# Snow_Melt_Map_2.net
KiCad netlist of a schematic drawn in EAGLE
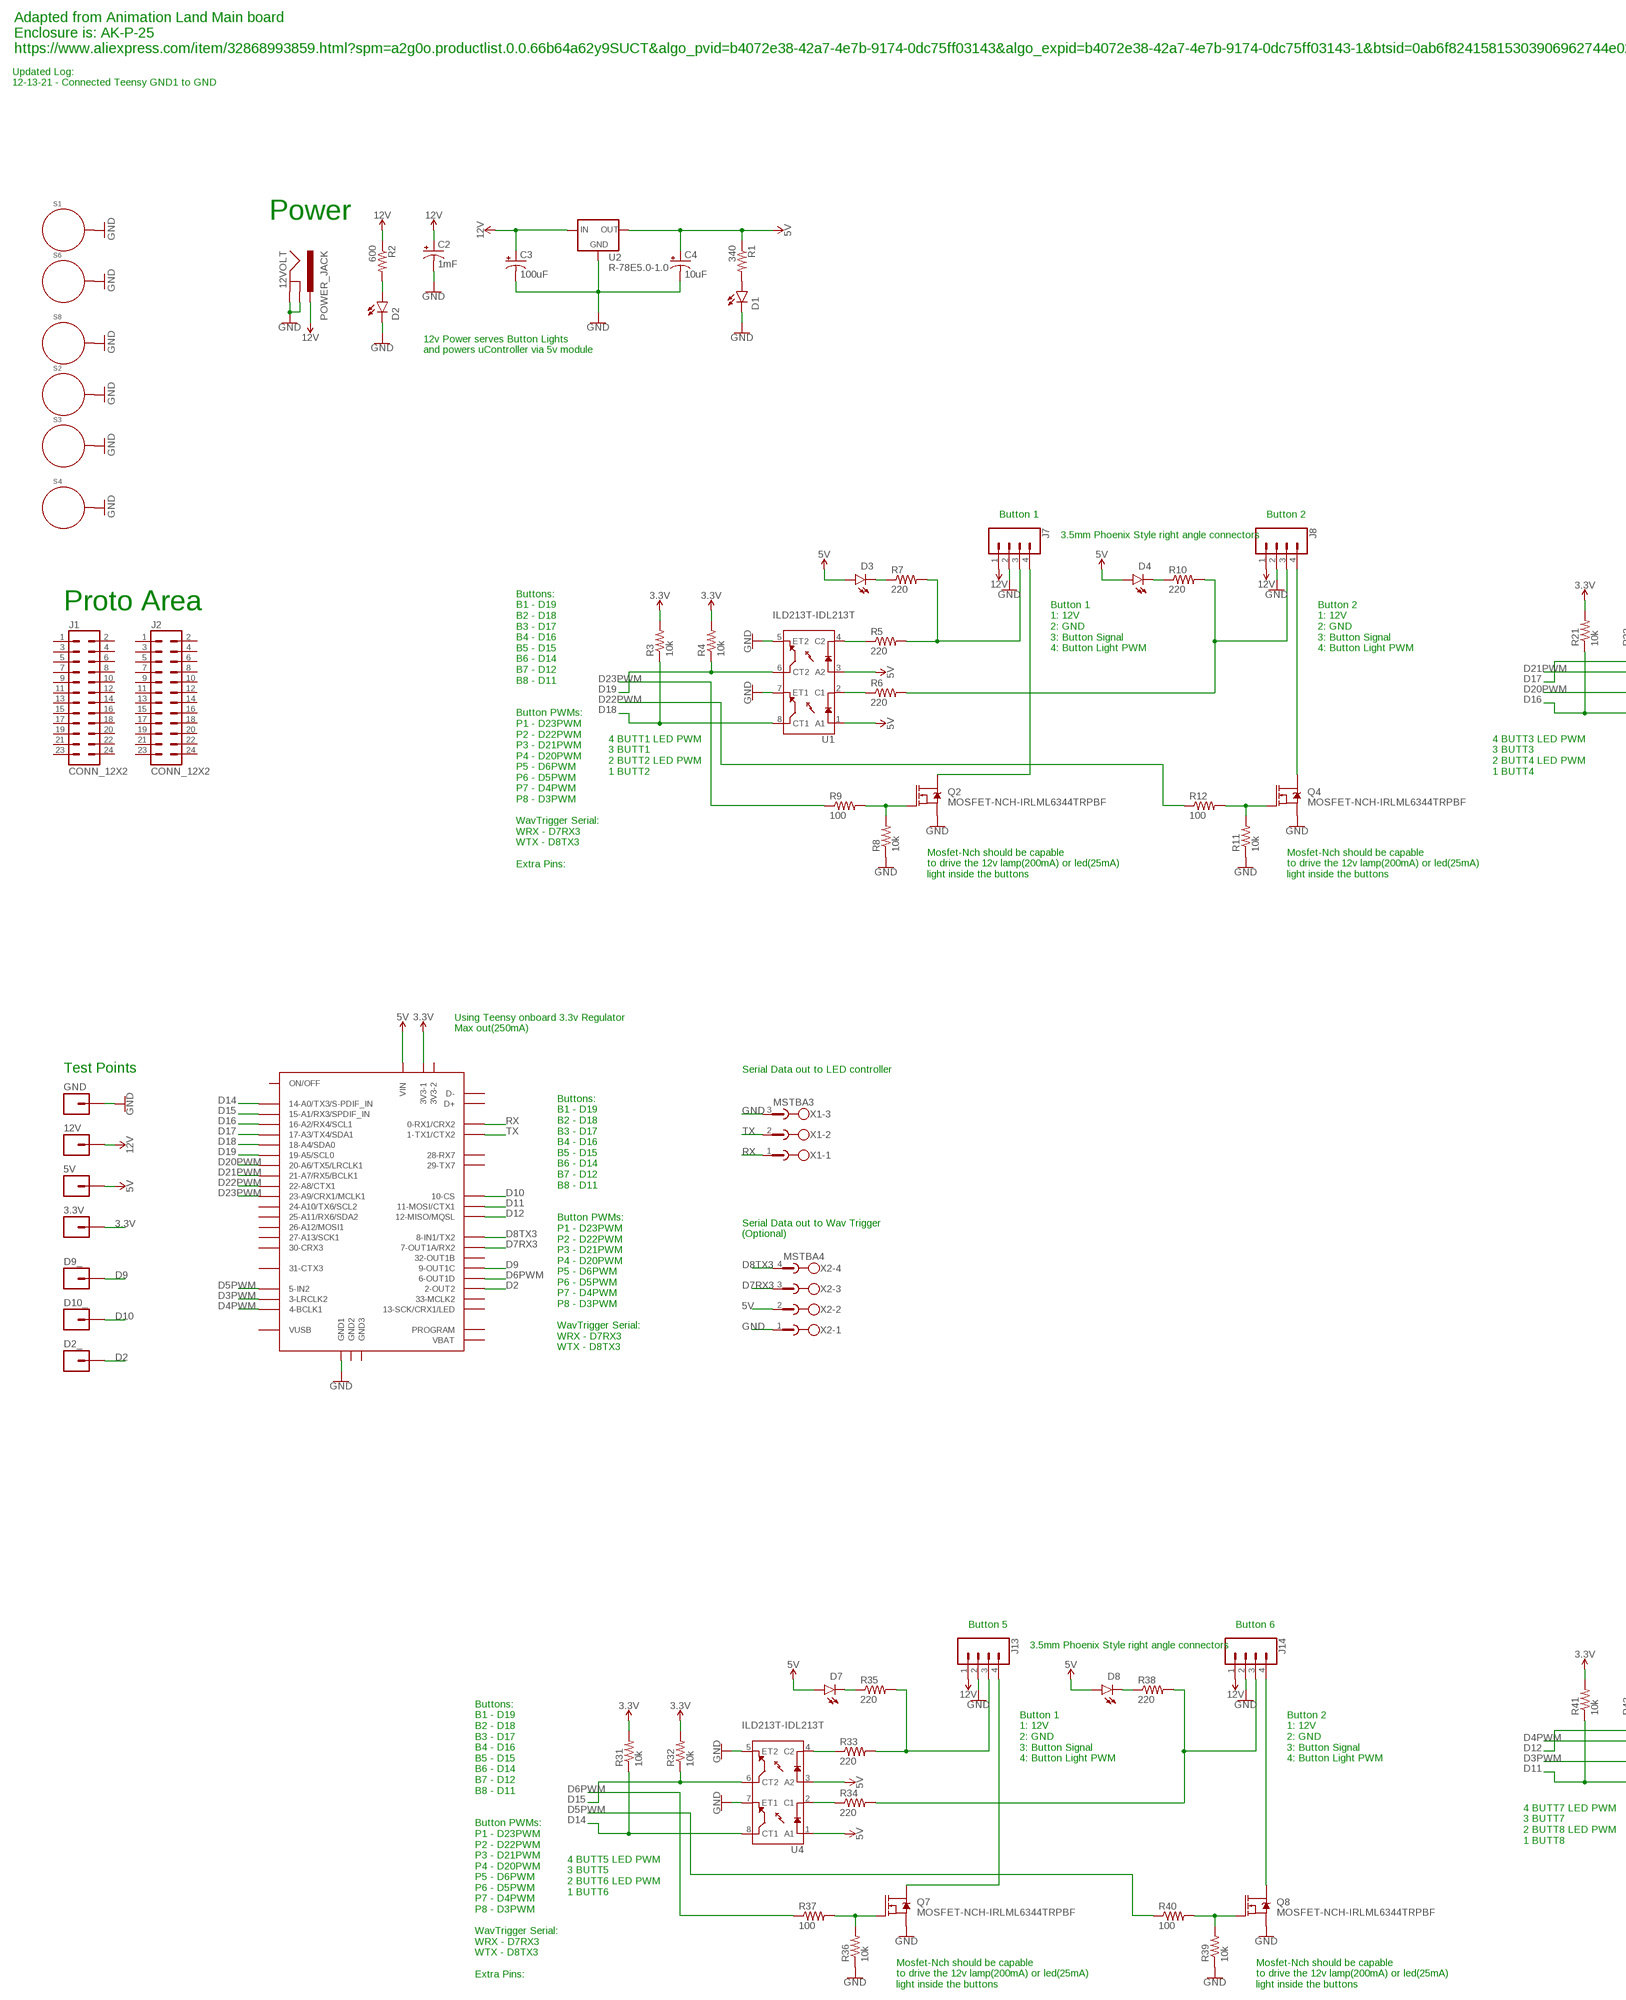
[diagram p0: schematic, sheet 1, part 1 of 2]
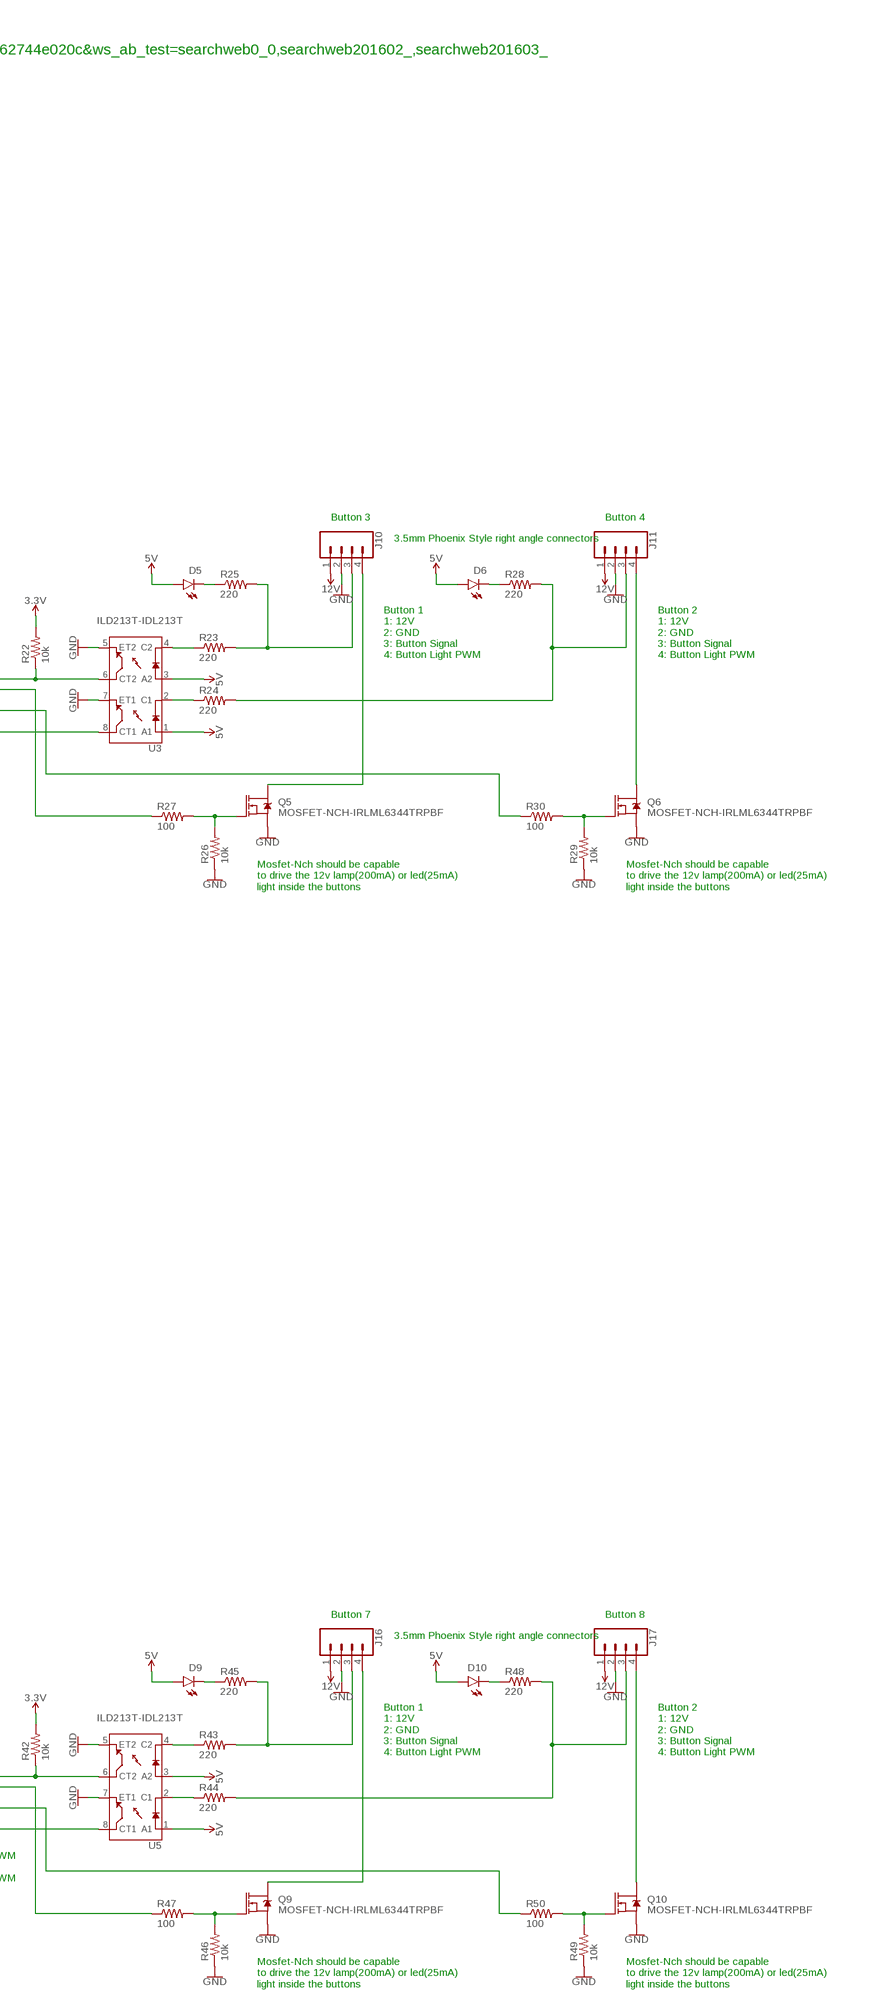
[diagram p1: schematic, sheet 1, part 2 of 2]

(export (version "E")
  (design (tool "Eeschema 10.0.6"))
  (components
    (comp (ref "3.3V")
      (value "M01PTH")
      (footprint "eagle-import:1X01")
      (libsource (lib "eagle-import") (part "M01PTH"))
    )
    (comp (ref "5V")
      (value "M01PTH")
      (footprint "eagle-import:1X01")
      (libsource (lib "eagle-import") (part "M01PTH"))
    )
    (comp (ref "12V")
      (value "M01PTH")
      (footprint "eagle-import:1X01")
      (libsource (lib "eagle-import") (part "M01PTH"))
    )
    (comp (ref "12VOLT")
      (value "POWER_JACK")
      (footprint "eagle-import:POWER_JACK_PTH")
      (libsource (lib "eagle-import") (part "POWER_JACK"))
    )
    (comp (ref "C2")
      (value "1mF")
      (footprint "eagle-import:CPOL-RADIAL-5MM-10MM")
      (libsource (lib "eagle-import") (part "1000UF-RADIAL-5MM-25V-20%"))
    )
    (comp (ref "C3")
      (value "100uF")
      (footprint "eagle-import:CPOL-RADIAL-2.5MM-6.5MM")
      (libsource (lib "eagle-import") (part "100UF-POLAR-RADIAL-2.5MM-25V-20%"))
    )
    (comp (ref "C4")
      (value "10uF")
      (footprint "eagle-import:CPOL-RADIAL-2.5MM-5MM-KIT")
      (libsource (lib "eagle-import") (part "10UF-POLAR-RADIAL-2.5MM-KIT-25V-20%"))
    )
    (comp (ref "D1")
      (value "RED")
      (footprint "eagle-import:LED-1206")
      (libsource (lib "eagle-import") (part "LED-RED1206"))
    )
    (comp (ref "D2")
      (value "RED")
      (footprint "eagle-import:LED-1206")
      (libsource (lib "eagle-import") (part "LED-RED1206"))
    )
    (comp (ref "D2_")
      (value "M01PTH")
      (footprint "eagle-import:1X01")
      (libsource (lib "eagle-import") (part "M01PTH"))
    )
    (comp (ref "D3")
      (value "RED")
      (footprint "eagle-import:LED-1206")
      (libsource (lib "eagle-import") (part "LED-RED1206"))
    )
    (comp (ref "D4")
      (value "RED")
      (footprint "eagle-import:LED-1206")
      (libsource (lib "eagle-import") (part "LED-RED1206"))
    )
    (comp (ref "D5")
      (value "RED")
      (footprint "eagle-import:LED-1206")
      (libsource (lib "eagle-import") (part "LED-RED1206"))
    )
    (comp (ref "D6")
      (value "RED")
      (footprint "eagle-import:LED-1206")
      (libsource (lib "eagle-import") (part "LED-RED1206"))
    )
    (comp (ref "D7")
      (value "RED")
      (footprint "eagle-import:LED-1206")
      (libsource (lib "eagle-import") (part "LED-RED1206"))
    )
    (comp (ref "D8")
      (value "RED")
      (footprint "eagle-import:LED-1206")
      (libsource (lib "eagle-import") (part "LED-RED1206"))
    )
    (comp (ref "D9")
      (value "RED")
      (footprint "eagle-import:LED-1206")
      (libsource (lib "eagle-import") (part "LED-RED1206"))
    )
    (comp (ref "D9_")
      (value "M01PTH")
      (footprint "eagle-import:1X01")
      (libsource (lib "eagle-import") (part "M01PTH"))
    )
    (comp (ref "D10")
      (value "RED")
      (footprint "eagle-import:LED-1206")
      (libsource (lib "eagle-import") (part "LED-RED1206"))
    )
    (comp (ref "D10_")
      (value "M01PTH")
      (footprint "eagle-import:1X01")
      (libsource (lib "eagle-import") (part "M01PTH"))
    )
    (comp (ref "GND")
      (value "M01PTH")
      (footprint "eagle-import:1X01")
      (libsource (lib "eagle-import") (part "M01PTH"))
    )
    (comp (ref "J1")
      (value "CONN_12X2")
      (footprint "eagle-import:2X12")
      (libsource (lib "eagle-import") (part "CONN_12X2"))
    )
    (comp (ref "J2")
      (value "CONN_12X2")
      (footprint "eagle-import:2X12")
      (libsource (lib "eagle-import") (part "CONN_12X2"))
    )
    (comp (ref "J7")
      (value "CONN_043.5MM_RA")
      (footprint "eagle-import:1X04_3.5MM_RA")
      (libsource (lib "eagle-import") (part "CONN_043.5MM_RA"))
    )
    (comp (ref "J8")
      (value "CONN_043.5MM_RA")
      (footprint "eagle-import:1X04_3.5MM_RA")
      (libsource (lib "eagle-import") (part "CONN_043.5MM_RA"))
    )
    (comp (ref "J10")
      (value "CONN_043.5MM_RA")
      (footprint "eagle-import:1X04_3.5MM_RA")
      (libsource (lib "eagle-import") (part "CONN_043.5MM_RA"))
    )
    (comp (ref "J11")
      (value "CONN_043.5MM_RA")
      (footprint "eagle-import:1X04_3.5MM_RA")
      (libsource (lib "eagle-import") (part "CONN_043.5MM_RA"))
    )
    (comp (ref "J13")
      (value "CONN_043.5MM_RA")
      (footprint "eagle-import:1X04_3.5MM_RA")
      (libsource (lib "eagle-import") (part "CONN_043.5MM_RA"))
    )
    (comp (ref "J14")
      (value "CONN_043.5MM_RA")
      (footprint "eagle-import:1X04_3.5MM_RA")
      (libsource (lib "eagle-import") (part "CONN_043.5MM_RA"))
    )
    (comp (ref "J16")
      (value "CONN_043.5MM_RA")
      (footprint "eagle-import:1X04_3.5MM_RA")
      (libsource (lib "eagle-import") (part "CONN_043.5MM_RA"))
    )
    (comp (ref "J17")
      (value "CONN_043.5MM_RA")
      (footprint "eagle-import:1X04_3.5MM_RA")
      (libsource (lib "eagle-import") (part "CONN_043.5MM_RA"))
    )
    (comp (ref "Q2")
      (value "MOSFET-NCH-IRLML6344TRPBF")
      (footprint "eagle-import:SOT23-3")
      (libsource (lib "eagle-import") (part "MOSFET-NCH-IRLML6344TRPBF"))
    )
    (comp (ref "Q4")
      (value "MOSFET-NCH-IRLML6344TRPBF")
      (footprint "eagle-import:SOT23-3")
      (libsource (lib "eagle-import") (part "MOSFET-NCH-IRLML6344TRPBF"))
    )
    (comp (ref "Q5")
      (value "MOSFET-NCH-IRLML6344TRPBF")
      (footprint "eagle-import:SOT23-3")
      (libsource (lib "eagle-import") (part "MOSFET-NCH-IRLML6344TRPBF"))
    )
    (comp (ref "Q6")
      (value "MOSFET-NCH-IRLML6344TRPBF")
      (footprint "eagle-import:SOT23-3")
      (libsource (lib "eagle-import") (part "MOSFET-NCH-IRLML6344TRPBF"))
    )
    (comp (ref "Q7")
      (value "MOSFET-NCH-IRLML6344TRPBF")
      (footprint "eagle-import:SOT23-3")
      (libsource (lib "eagle-import") (part "MOSFET-NCH-IRLML6344TRPBF"))
    )
    (comp (ref "Q8")
      (value "MOSFET-NCH-IRLML6344TRPBF")
      (footprint "eagle-import:SOT23-3")
      (libsource (lib "eagle-import") (part "MOSFET-NCH-IRLML6344TRPBF"))
    )
    (comp (ref "Q9")
      (value "MOSFET-NCH-IRLML6344TRPBF")
      (footprint "eagle-import:SOT23-3")
      (libsource (lib "eagle-import") (part "MOSFET-NCH-IRLML6344TRPBF"))
    )
    (comp (ref "Q10")
      (value "MOSFET-NCH-IRLML6344TRPBF")
      (footprint "eagle-import:SOT23-3")
      (libsource (lib "eagle-import") (part "MOSFET-NCH-IRLML6344TRPBF"))
    )
    (comp (ref "R1")
      (value "340")
      (footprint "eagle-import:R0805")
      (libsource (lib "eagle-import") (part "R-US_R0805"))
    )
    (comp (ref "R2")
      (value "600")
      (footprint "eagle-import:R0805")
      (libsource (lib "eagle-import") (part "R-US_R0805"))
    )
    (comp (ref "R3")
      (value "10k")
      (footprint "eagle-import:R0805")
      (libsource (lib "eagle-import") (part "R-US_R0805"))
    )
    (comp (ref "R4")
      (value "10k")
      (footprint "eagle-import:R0805")
      (libsource (lib "eagle-import") (part "R-US_R0805"))
    )
    (comp (ref "R5")
      (value "220")
      (footprint "eagle-import:R0805")
      (libsource (lib "eagle-import") (part "R-US_R0805"))
    )
    (comp (ref "R6")
      (value "220")
      (footprint "eagle-import:R0805")
      (libsource (lib "eagle-import") (part "R-US_R0805"))
    )
    (comp (ref "R7")
      (value "220")
      (footprint "eagle-import:R0805")
      (libsource (lib "eagle-import") (part "R-US_R0805"))
    )
    (comp (ref "R8")
      (value "10k")
      (footprint "eagle-import:R0805")
      (libsource (lib "eagle-import") (part "R-US_R0805"))
    )
    (comp (ref "R9")
      (value "100")
      (footprint "eagle-import:R0805")
      (libsource (lib "eagle-import") (part "R-US_R0805"))
    )
    (comp (ref "R10")
      (value "220")
      (footprint "eagle-import:R0805")
      (libsource (lib "eagle-import") (part "R-US_R0805"))
    )
    (comp (ref "R11")
      (value "10k")
      (footprint "eagle-import:R0805")
      (libsource (lib "eagle-import") (part "R-US_R0805"))
    )
    (comp (ref "R12")
      (value "100")
      (footprint "eagle-import:R0805")
      (libsource (lib "eagle-import") (part "R-US_R0805"))
    )
    (comp (ref "R21")
      (value "10k")
      (footprint "eagle-import:R0805")
      (libsource (lib "eagle-import") (part "R-US_R0805"))
    )
    (comp (ref "R22")
      (value "10k")
      (footprint "eagle-import:R0805")
      (libsource (lib "eagle-import") (part "R-US_R0805"))
    )
    (comp (ref "R23")
      (value "220")
      (footprint "eagle-import:R0805")
      (libsource (lib "eagle-import") (part "R-US_R0805"))
    )
    (comp (ref "R24")
      (value "220")
      (footprint "eagle-import:R0805")
      (libsource (lib "eagle-import") (part "R-US_R0805"))
    )
    (comp (ref "R25")
      (value "220")
      (footprint "eagle-import:R0805")
      (libsource (lib "eagle-import") (part "R-US_R0805"))
    )
    (comp (ref "R26")
      (value "10k")
      (footprint "eagle-import:R0805")
      (libsource (lib "eagle-import") (part "R-US_R0805"))
    )
    (comp (ref "R27")
      (value "100")
      (footprint "eagle-import:R0805")
      (libsource (lib "eagle-import") (part "R-US_R0805"))
    )
    (comp (ref "R28")
      (value "220")
      (footprint "eagle-import:R0805")
      (libsource (lib "eagle-import") (part "R-US_R0805"))
    )
    (comp (ref "R29")
      (value "10k")
      (footprint "eagle-import:R0805")
      (libsource (lib "eagle-import") (part "R-US_R0805"))
    )
    (comp (ref "R30")
      (value "100")
      (footprint "eagle-import:R0805")
      (libsource (lib "eagle-import") (part "R-US_R0805"))
    )
    (comp (ref "R31")
      (value "10k")
      (footprint "eagle-import:R0805")
      (libsource (lib "eagle-import") (part "R-US_R0805"))
    )
    (comp (ref "R32")
      (value "10k")
      (footprint "eagle-import:R0805")
      (libsource (lib "eagle-import") (part "R-US_R0805"))
    )
    (comp (ref "R33")
      (value "220")
      (footprint "eagle-import:R0805")
      (libsource (lib "eagle-import") (part "R-US_R0805"))
    )
    (comp (ref "R34")
      (value "220")
      (footprint "eagle-import:R0805")
      (libsource (lib "eagle-import") (part "R-US_R0805"))
    )
    (comp (ref "R35")
      (value "220")
      (footprint "eagle-import:R0805")
      (libsource (lib "eagle-import") (part "R-US_R0805"))
    )
    (comp (ref "R36")
      (value "10k")
      (footprint "eagle-import:R0805")
      (libsource (lib "eagle-import") (part "R-US_R0805"))
    )
    (comp (ref "R37")
      (value "100")
      (footprint "eagle-import:R0805")
      (libsource (lib "eagle-import") (part "R-US_R0805"))
    )
    (comp (ref "R38")
      (value "220")
      (footprint "eagle-import:R0805")
      (libsource (lib "eagle-import") (part "R-US_R0805"))
    )
    (comp (ref "R39")
      (value "10k")
      (footprint "eagle-import:R0805")
      (libsource (lib "eagle-import") (part "R-US_R0805"))
    )
    (comp (ref "R40")
      (value "100")
      (footprint "eagle-import:R0805")
      (libsource (lib "eagle-import") (part "R-US_R0805"))
    )
    (comp (ref "R41")
      (value "10k")
      (footprint "eagle-import:R0805")
      (libsource (lib "eagle-import") (part "R-US_R0805"))
    )
    (comp (ref "R42")
      (value "10k")
      (footprint "eagle-import:R0805")
      (libsource (lib "eagle-import") (part "R-US_R0805"))
    )
    (comp (ref "R43")
      (value "220")
      (footprint "eagle-import:R0805")
      (libsource (lib "eagle-import") (part "R-US_R0805"))
    )
    (comp (ref "R44")
      (value "220")
      (footprint "eagle-import:R0805")
      (libsource (lib "eagle-import") (part "R-US_R0805"))
    )
    (comp (ref "R45")
      (value "220")
      (footprint "eagle-import:R0805")
      (libsource (lib "eagle-import") (part "R-US_R0805"))
    )
    (comp (ref "R46")
      (value "10k")
      (footprint "eagle-import:R0805")
      (libsource (lib "eagle-import") (part "R-US_R0805"))
    )
    (comp (ref "R47")
      (value "100")
      (footprint "eagle-import:R0805")
      (libsource (lib "eagle-import") (part "R-US_R0805"))
    )
    (comp (ref "R48")
      (value "220")
      (footprint "eagle-import:R0805")
      (libsource (lib "eagle-import") (part "R-US_R0805"))
    )
    (comp (ref "R49")
      (value "10k")
      (footprint "eagle-import:R0805")
      (libsource (lib "eagle-import") (part "R-US_R0805"))
    )
    (comp (ref "R50")
      (value "100")
      (footprint "eagle-import:R0805")
      (libsource (lib "eagle-import") (part "R-US_R0805"))
    )
    (comp (ref "S1")
      (value "STANDOFF_ELECTRICAL5-32")
      (footprint "eagle-import:STANDOFF_ELECTRICAL_5_32")
      (libsource (lib "eagle-import") (part "STANDOFF_ELECTRICAL5-32"))
    )
    (comp (ref "S2")
      (value "STANDOFF_ELECTRICAL5-32")
      (footprint "eagle-import:STANDOFF_ELECTRICAL_5_32")
      (libsource (lib "eagle-import") (part "STANDOFF_ELECTRICAL5-32"))
    )
    (comp (ref "S3")
      (value "STANDOFF_ELECTRICAL5-32")
      (footprint "eagle-import:STANDOFF_ELECTRICAL_5_32")
      (libsource (lib "eagle-import") (part "STANDOFF_ELECTRICAL5-32"))
    )
    (comp (ref "S4")
      (value "STANDOFF_ELECTRICAL5-32")
      (footprint "eagle-import:STANDOFF_ELECTRICAL_5_32")
      (libsource (lib "eagle-import") (part "STANDOFF_ELECTRICAL5-32"))
    )
    (comp (ref "S6")
      (value "STANDOFF_ELECTRICAL5-32")
      (footprint "eagle-import:STANDOFF_ELECTRICAL_5_32")
      (libsource (lib "eagle-import") (part "STANDOFF_ELECTRICAL5-32"))
    )
    (comp (ref "S8")
      (value "STANDOFF_ELECTRICAL5-32")
      (footprint "eagle-import:STANDOFF_ELECTRICAL_5_32")
      (libsource (lib "eagle-import") (part "STANDOFF_ELECTRICAL5-32"))
    )
    (comp (ref "U$1")
      (value "TEENSY40")
      (footprint "eagle-import:TEENSY40")
      (libsource (lib "eagle-import") (part "TEENSY40"))
    )
    (comp (ref "U1")
      (value "ILD213T-IDL213T")
      (footprint "eagle-import:SO08")
      (libsource (lib "eagle-import") (part "ILD213T-IDL213T"))
    )
    (comp (ref "U2")
      (value "R-78E5.0-1.0")
      (footprint "eagle-import:DC-DC_CONVERTER_78XX")
      (libsource (lib "eagle-import") (part "R-78E5.0-1.0"))
    )
    (comp (ref "U3")
      (value "ILD213T-IDL213T")
      (footprint "eagle-import:SO08")
      (libsource (lib "eagle-import") (part "ILD213T-IDL213T"))
    )
    (comp (ref "U4")
      (value "ILD213T-IDL213T")
      (footprint "eagle-import:SO08")
      (libsource (lib "eagle-import") (part "ILD213T-IDL213T"))
    )
    (comp (ref "U5")
      (value "ILD213T-IDL213T")
      (footprint "eagle-import:SO08")
      (libsource (lib "eagle-import") (part "ILD213T-IDL213T"))
    )
    (comp (ref "X1")
      (value "MSTBA3")
      (footprint "eagle-import:MSTBA3")
      (fields (field (name "MF") "FARNELL") (field (name "MPN") "1757255"))
      (libsource (lib "eagle-import") (part "MSTBA3"))
    )
    (comp (ref "X2")
      (value "MSTBA4")
      (footprint "eagle-import:MSTBA4")
      (fields (field (name "MF") "FARNELL") (field (name "MPN") "1757268"))
      (libsource (lib "eagle-import") (part "MSTBA4"))
    )
  )
  (nets
    (net (code "1") (name "/D2") (class "Default")
      (node (ref "D2_") (pin "1") (pinfunction "1_1") (pintype "passive"))
      (node (ref "U$1") (pin "2-OUT2") (pinfunction "2-OUT2_2-OUT2") (pintype "bidirectional"))
    )
    (net (code "2") (name "/D3PWM") (class "Default")
      (node (ref "R50") (pin "1") (pinfunction "1_1") (pintype "passive"))
      (node (ref "U$1") (pin "3-LRCLK2") (pinfunction "3-LRCLK2_3-LRCLK2") (pintype "bidirectional"))
    )
    (net (code "3") (name "/D4PWM") (class "Default")
      (node (ref "R47") (pin "1") (pinfunction "1_1") (pintype "passive"))
      (node (ref "U$1") (pin "4-BCLK2") (pinfunction "4-BCLK1_4-BCLK2") (pintype "bidirectional"))
    )
    (net (code "4") (name "/D5PWM") (class "Default")
      (node (ref "R40") (pin "1") (pinfunction "1_1") (pintype "passive"))
      (node (ref "U$1") (pin "5-IN2") (pinfunction "5-IN2_5-IN2") (pintype "bidirectional"))
    )
    (net (code "5") (name "/D6PWM") (class "Default")
      (node (ref "R37") (pin "1") (pinfunction "1_1") (pintype "passive"))
      (node (ref "U$1") (pin "6-OUT1D") (pinfunction "6-OUT1D_6-OUT1D") (pintype "bidirectional"))
    )
    (net (code "6") (name "/D7RX3") (class "Default")
      (node (ref "U$1") (pin "7-RX2/OUT1A") (pinfunction "7-OUT1A/RX2_7-RX2/OUT1A") (pintype "bidirectional"))
      (node (ref "X2") (pin "3") (pinfunction "1_3") (pintype "passive"))
    )
    (net (code "7") (name "/D8TX3") (class "Default")
      (node (ref "U$1") (pin "8-TX2/IN1") (pinfunction "8-IN1/TX2_8-TX2/IN1") (pintype "bidirectional"))
      (node (ref "X2") (pin "4") (pinfunction "1_4") (pintype "passive"))
    )
    (net (code "8") (name "/D9") (class "Default")
      (node (ref "D9_") (pin "1") (pinfunction "1_1") (pintype "passive"))
      (node (ref "U$1") (pin "9-OUT1C") (pinfunction "9-OUT1C_9-OUT1C") (pintype "bidirectional"))
    )
    (net (code "9") (name "/D10") (class "Default")
      (node (ref "D10_") (pin "1") (pinfunction "1_1") (pintype "passive"))
      (node (ref "U$1") (pin "10-CS/MQSR") (pinfunction "10-CS_10-CS/MQSR") (pintype "bidirectional"))
    )
    (net (code "10") (name "/D11") (class "Default")
      (node (ref "R41") (pin "1") (pinfunction "1_1") (pintype "passive"))
      (node (ref "U$1") (pin "11-MOSI/CTX1") (pinfunction "11-MOSI/CTX1_11-MOSI/CTX1") (pintype "bidirectional"))
      (node (ref "U5") (pin "8") (pinfunction "CT1_8") (pintype "bidirectional"))
    )
    (net (code "11") (name "/D12") (class "Default")
      (node (ref "R42") (pin "1") (pinfunction "1_1") (pintype "passive"))
      (node (ref "U$1") (pin "12-MIO/MQSL") (pinfunction "12-MISO/MQSL_12-MIO/MQSL") (pintype "bidirectional"))
      (node (ref "U5") (pin "6") (pinfunction "CT2_6") (pintype "bidirectional"))
    )
    (net (code "12") (name "/D14") (class "Default")
      (node (ref "R31") (pin "1") (pinfunction "1_1") (pintype "passive"))
      (node (ref "U$1") (pin "14-A0/TX3/S-PFI_OUT") (pinfunction "14-A0/TX3/S-PDIF_IN_14-A0/TX3/S-PFI_OUT") (pintype "bidirectional"))
      (node (ref "U4") (pin "8") (pinfunction "CT1_8") (pintype "bidirectional"))
    )
    (net (code "13") (name "/D15") (class "Default")
      (node (ref "R32") (pin "1") (pinfunction "1_1") (pintype "passive"))
      (node (ref "U$1") (pin "15-A1/RX3/S-PDIF_IN") (pinfunction "15-A1/RX3/SPDIF_IN_15-A1/RX3/S-PDIF_IN") (pintype "bidirectional"))
      (node (ref "U4") (pin "6") (pinfunction "CT2_6") (pintype "bidirectional"))
    )
    (net (code "14") (name "/D16") (class "Default")
      (node (ref "R21") (pin "1") (pinfunction "1_1") (pintype "passive"))
      (node (ref "U$1") (pin "16-A2/RX4/SCL1") (pinfunction "16-A2/RX4/SCL1_16-A2/RX4/SCL1") (pintype "bidirectional"))
      (node (ref "U3") (pin "8") (pinfunction "CT1_8") (pintype "bidirectional"))
    )
    (net (code "15") (name "/D17") (class "Default")
      (node (ref "R22") (pin "1") (pinfunction "1_1") (pintype "passive"))
      (node (ref "U$1") (pin "17-A3/TX4/SDA1") (pinfunction "17-A3/TX4/SDA1_17-A3/TX4/SDA1") (pintype "bidirectional"))
      (node (ref "U3") (pin "6") (pinfunction "CT2_6") (pintype "bidirectional"))
    )
    (net (code "16") (name "/D18") (class "Default")
      (node (ref "R3") (pin "1") (pinfunction "1_1") (pintype "passive"))
      (node (ref "U$1") (pin "18-A4/SDA0") (pinfunction "18-A4/SDA0_18-A4/SDA0") (pintype "bidirectional"))
      (node (ref "U1") (pin "8") (pinfunction "CT1_8") (pintype "bidirectional"))
    )
    (net (code "17") (name "/D19") (class "Default")
      (node (ref "R4") (pin "1") (pinfunction "1_1") (pintype "passive"))
      (node (ref "U$1") (pin "19-A5/SCL0") (pinfunction "19-A5/SCL0_19-A5/SCL0") (pintype "bidirectional"))
      (node (ref "U1") (pin "6") (pinfunction "CT2_6") (pintype "bidirectional"))
    )
    (net (code "18") (name "/D20PWM") (class "Default")
      (node (ref "R30") (pin "1") (pinfunction "1_1") (pintype "passive"))
      (node (ref "U$1") (pin "20-A6/TX5/LRCLK1") (pinfunction "20-A6/TX5/LRCLK1_20-A6/TX5/LRCLK1") (pintype "bidirectional"))
    )
    (net (code "19") (name "/D21PWM") (class "Default")
      (node (ref "R27") (pin "1") (pinfunction "1_1") (pintype "passive"))
      (node (ref "U$1") (pin "21-A7/RX5/BCLK1") (pinfunction "21-A7/RX5/BCLK1_21-A7/RX5/BCLK1") (pintype "bidirectional"))
    )
    (net (code "20") (name "/D22PWM") (class "Default")
      (node (ref "R12") (pin "1") (pinfunction "1_1") (pintype "passive"))
      (node (ref "U$1") (pin "22-A8/CTX1") (pinfunction "22-A8/CTX1_22-A8/CTX1") (pintype "bidirectional"))
    )
    (net (code "21") (name "/D23PWM") (class "Default")
      (node (ref "R9") (pin "1") (pinfunction "1_1") (pintype "passive"))
      (node (ref "U$1") (pin "23-A9/CRX1/CCLK1") (pinfunction "23-A9/CRX1/MCLK1_23-A9/CRX1/CCLK1") (pintype "bidirectional"))
    )
    (net (code "22") (name "/RX") (class "Default")
      (node (ref "U$1") (pin "0-RX1") (pinfunction "0-RX1/CRX2_0-RX1") (pintype "bidirectional"))
      (node (ref "X1") (pin "1") (pinfunction "1_1") (pintype "passive"))
    )
    (net (code "23") (name "/TX") (class "Default")
      (node (ref "U$1") (pin "1-TX1") (pinfunction "1-TX1/CTX2_1-TX1") (pintype "bidirectional"))
      (node (ref "X1") (pin "2") (pinfunction "1_2") (pintype "passive"))
    )
    (net (code "24") (name "3.3V") (class "Default")
      (node (ref "3.3V") (pin "1") (pinfunction "1_1") (pintype "passive"))
      (node (ref "R21") (pin "2") (pinfunction "2_2") (pintype "passive"))
      (node (ref "R22") (pin "2") (pinfunction "2_2") (pintype "passive"))
      (node (ref "R3") (pin "2") (pinfunction "2_2") (pintype "passive"))
      (node (ref "R31") (pin "2") (pinfunction "2_2") (pintype "passive"))
      (node (ref "R32") (pin "2") (pinfunction "2_2") (pintype "passive"))
      (node (ref "R4") (pin "2") (pinfunction "2_2") (pintype "passive"))
      (node (ref "R41") (pin "2") (pinfunction "2_2") (pintype "passive"))
      (node (ref "R42") (pin "2") (pinfunction "2_2") (pintype "passive"))
      (node (ref "U$1") (pin "3V3-1") (pinfunction "3V3-1_3V3-1") (pintype "bidirectional"))
    )
    (net (code "25") (name "5V") (class "Default")
      (node (ref "5V") (pin "1") (pinfunction "1_1") (pintype "passive"))
      (node (ref "C4") (pin "1") (pinfunction "+_1") (pintype "passive"))
      (node (ref "D10") (pin "A") (pinfunction "A_A") (pintype "passive"))
      (node (ref "D3") (pin "A") (pinfunction "A_A") (pintype "passive"))
      (node (ref "D4") (pin "A") (pinfunction "A_A") (pintype "passive"))
      (node (ref "D5") (pin "A") (pinfunction "A_A") (pintype "passive"))
      (node (ref "D6") (pin "A") (pinfunction "A_A") (pintype "passive"))
      (node (ref "D7") (pin "A") (pinfunction "A_A") (pintype "passive"))
      (node (ref "D8") (pin "A") (pinfunction "A_A") (pintype "passive"))
      (node (ref "D9") (pin "A") (pinfunction "A_A") (pintype "passive"))
      (node (ref "R1") (pin "1") (pinfunction "1_1") (pintype "passive"))
      (node (ref "U$1") (pin "VIN") (pinfunction "VIN_VIN") (pintype "bidirectional"))
      (node (ref "U1") (pin "1") (pinfunction "A1_1") (pintype "bidirectional"))
      (node (ref "U1") (pin "3") (pinfunction "A2_3") (pintype "bidirectional"))
      (node (ref "U2") (pin "VOUT") (pinfunction "OUT_VOUT") (pintype "passive"))
      (node (ref "U3") (pin "1") (pinfunction "A1_1") (pintype "bidirectional"))
      (node (ref "U3") (pin "3") (pinfunction "A2_3") (pintype "bidirectional"))
      (node (ref "U4") (pin "1") (pinfunction "A1_1") (pintype "bidirectional"))
      (node (ref "U4") (pin "3") (pinfunction "A2_3") (pintype "bidirectional"))
      (node (ref "U5") (pin "1") (pinfunction "A1_1") (pintype "bidirectional"))
      (node (ref "U5") (pin "3") (pinfunction "A2_3") (pintype "bidirectional"))
      (node (ref "X2") (pin "2") (pinfunction "1_2") (pintype "passive"))
    )
    (net (code "26") (name "12V") (class "Default")
      (node (ref "12V") (pin "1") (pinfunction "1_1") (pintype "passive"))
      (node (ref "12VOLT") (pin "PWR") (pinfunction "PWR_PWR") (pintype "bidirectional"))
      (node (ref "C2") (pin "+") (pinfunction "+_+") (pintype "passive"))
      (node (ref "C3") (pin "1") (pinfunction "+_1") (pintype "passive"))
      (node (ref "J10") (pin "1") (pinfunction "1_1") (pintype "passive"))
      (node (ref "J11") (pin "1") (pinfunction "1_1") (pintype "passive"))
      (node (ref "J13") (pin "1") (pinfunction "1_1") (pintype "passive"))
      (node (ref "J14") (pin "1") (pinfunction "1_1") (pintype "passive"))
      (node (ref "J16") (pin "1") (pinfunction "1_1") (pintype "passive"))
      (node (ref "J17") (pin "1") (pinfunction "1_1") (pintype "passive"))
      (node (ref "J7") (pin "1") (pinfunction "1_1") (pintype "passive"))
      (node (ref "J8") (pin "1") (pinfunction "1_1") (pintype "passive"))
      (node (ref "R2") (pin "1") (pinfunction "1_1") (pintype "passive"))
      (node (ref "U2") (pin "VIN") (pinfunction "IN_VIN") (pintype "input"))
    )
    (net (code "27") (name "GND") (class "Default")
      (node (ref "12VOLT") (pin "GND") (pinfunction "GND_GND") (pintype "bidirectional"))
      (node (ref "12VOLT") (pin "GNDBREAK") (pinfunction "GNDBREAK_GNDBREAK") (pintype "bidirectional"))
      (node (ref "C2") (pin "-") (pinfunction "-_-") (pintype "passive"))
      (node (ref "C3") (pin "2") (pinfunction "-_2") (pintype "passive"))
      (node (ref "C4") (pin "2") (pinfunction "-_2") (pintype "passive"))
      (node (ref "D1") (pin "C") (pinfunction "C_C") (pintype "passive"))
      (node (ref "D2") (pin "C") (pinfunction "C_C") (pintype "passive"))
      (node (ref "GND") (pin "1") (pinfunction "1_1") (pintype "passive"))
      (node (ref "J10") (pin "2") (pinfunction "2_2") (pintype "passive"))
      (node (ref "J11") (pin "2") (pinfunction "2_2") (pintype "passive"))
      (node (ref "J13") (pin "2") (pinfunction "2_2") (pintype "passive"))
      (node (ref "J14") (pin "2") (pinfunction "2_2") (pintype "passive"))
      (node (ref "J16") (pin "2") (pinfunction "2_2") (pintype "passive"))
      (node (ref "J17") (pin "2") (pinfunction "2_2") (pintype "passive"))
      (node (ref "J7") (pin "2") (pinfunction "2_2") (pintype "passive"))
      (node (ref "J8") (pin "2") (pinfunction "2_2") (pintype "passive"))
      (node (ref "Q10") (pin "2") (pinfunction "S_2") (pintype "bidirectional"))
      (node (ref "Q2") (pin "2") (pinfunction "S_2") (pintype "bidirectional"))
      (node (ref "Q4") (pin "2") (pinfunction "S_2") (pintype "bidirectional"))
      (node (ref "Q5") (pin "2") (pinfunction "S_2") (pintype "bidirectional"))
      (node (ref "Q6") (pin "2") (pinfunction "S_2") (pintype "bidirectional"))
      (node (ref "Q7") (pin "2") (pinfunction "S_2") (pintype "bidirectional"))
      (node (ref "Q8") (pin "2") (pinfunction "S_2") (pintype "bidirectional"))
      (node (ref "Q9") (pin "2") (pinfunction "S_2") (pintype "bidirectional"))
      (node (ref "R11") (pin "1") (pinfunction "1_1") (pintype "passive"))
      (node (ref "R26") (pin "1") (pinfunction "1_1") (pintype "passive"))
      (node (ref "R29") (pin "1") (pinfunction "1_1") (pintype "passive"))
      (node (ref "R36") (pin "1") (pinfunction "1_1") (pintype "passive"))
      (node (ref "R39") (pin "1") (pinfunction "1_1") (pintype "passive"))
      (node (ref "R46") (pin "1") (pinfunction "1_1") (pintype "passive"))
      (node (ref "R49") (pin "1") (pinfunction "1_1") (pintype "passive"))
      (node (ref "R8") (pin "1") (pinfunction "1_1") (pintype "passive"))
      (node (ref "S1") (pin "P1") (pinfunction "P$1_P1") (pintype "bidirectional"))
      (node (ref "S2") (pin "P1") (pinfunction "P$1_P1") (pintype "bidirectional"))
      (node (ref "S3") (pin "P1") (pinfunction "P$1_P1") (pintype "bidirectional"))
      (node (ref "S4") (pin "P1") (pinfunction "P$1_P1") (pintype "bidirectional"))
      (node (ref "S6") (pin "P1") (pinfunction "P$1_P1") (pintype "bidirectional"))
      (node (ref "S8") (pin "P1") (pinfunction "P$1_P1") (pintype "bidirectional"))
      (node (ref "U$1") (pin "GND1") (pinfunction "GND1_GND1") (pintype "bidirectional"))
      (node (ref "U1") (pin "5") (pinfunction "ET2_5") (pintype "bidirectional"))
      (node (ref "U1") (pin "7") (pinfunction "ET1_7") (pintype "bidirectional"))
      (node (ref "U2") (pin "GND") (pinfunction "GND_GND") (pintype "input"))
      (node (ref "U3") (pin "5") (pinfunction "ET2_5") (pintype "bidirectional"))
      (node (ref "U3") (pin "7") (pinfunction "ET1_7") (pintype "bidirectional"))
      (node (ref "U4") (pin "5") (pinfunction "ET2_5") (pintype "bidirectional"))
      (node (ref "U4") (pin "7") (pinfunction "ET1_7") (pintype "bidirectional"))
      (node (ref "U5") (pin "5") (pinfunction "ET2_5") (pintype "bidirectional"))
      (node (ref "U5") (pin "7") (pinfunction "ET1_7") (pintype "bidirectional"))
      (node (ref "X1") (pin "3") (pinfunction "1_3") (pintype "passive"))
      (node (ref "X2") (pin "1") (pinfunction "1_1") (pintype "passive"))
    )
    (net (code "28") (name "Net-(D1-PadA)") (class "Default")
      (node (ref "D1") (pin "A") (pinfunction "A_A") (pintype "passive"))
      (node (ref "R1") (pin "2") (pinfunction "2_2") (pintype "passive"))
    )
    (net (code "29") (name "Net-(D2-PadA)") (class "Default")
      (node (ref "D2") (pin "A") (pinfunction "A_A") (pintype "passive"))
      (node (ref "R2") (pin "2") (pinfunction "2_2") (pintype "passive"))
    )
    (net (code "30") (name "Net-(D3-PadC)") (class "Default")
      (node (ref "D3") (pin "C") (pinfunction "C_C") (pintype "passive"))
      (node (ref "R7") (pin "1") (pinfunction "1_1") (pintype "passive"))
    )
    (net (code "31") (name "Net-(D4-PadC)") (class "Default")
      (node (ref "D4") (pin "C") (pinfunction "C_C") (pintype "passive"))
      (node (ref "R10") (pin "1") (pinfunction "1_1") (pintype "passive"))
    )
    (net (code "32") (name "Net-(D5-PadC)") (class "Default")
      (node (ref "D5") (pin "C") (pinfunction "C_C") (pintype "passive"))
      (node (ref "R25") (pin "1") (pinfunction "1_1") (pintype "passive"))
    )
    (net (code "33") (name "Net-(D6-PadC)") (class "Default")
      (node (ref "D6") (pin "C") (pinfunction "C_C") (pintype "passive"))
      (node (ref "R28") (pin "1") (pinfunction "1_1") (pintype "passive"))
    )
    (net (code "34") (name "Net-(D7-PadC)") (class "Default")
      (node (ref "D7") (pin "C") (pinfunction "C_C") (pintype "passive"))
      (node (ref "R35") (pin "1") (pinfunction "1_1") (pintype "passive"))
    )
    (net (code "35") (name "Net-(D8-PadC)") (class "Default")
      (node (ref "D8") (pin "C") (pinfunction "C_C") (pintype "passive"))
      (node (ref "R38") (pin "1") (pinfunction "1_1") (pintype "passive"))
    )
    (net (code "36") (name "Net-(D9-PadC)") (class "Default")
      (node (ref "D9") (pin "C") (pinfunction "C_C") (pintype "passive"))
      (node (ref "R45") (pin "1") (pinfunction "1_1") (pintype "passive"))
    )
    (net (code "37") (name "Net-(D10-PadC)") (class "Default")
      (node (ref "D10") (pin "C") (pinfunction "C_C") (pintype "passive"))
      (node (ref "R48") (pin "1") (pinfunction "1_1") (pintype "passive"))
    )
    (net (code "38") (name "Net-(J7-Pad3)") (class "Default")
      (node (ref "J7") (pin "3") (pinfunction "3_3") (pintype "passive"))
      (node (ref "R5") (pin "2") (pinfunction "2_2") (pintype "passive"))
      (node (ref "R7") (pin "2") (pinfunction "2_2") (pintype "passive"))
    )
    (net (code "39") (name "Net-(J8-Pad3)") (class "Default")
      (node (ref "J8") (pin "3") (pinfunction "3_3") (pintype "passive"))
      (node (ref "R10") (pin "2") (pinfunction "2_2") (pintype "passive"))
      (node (ref "R6") (pin "2") (pinfunction "2_2") (pintype "passive"))
    )
    (net (code "40") (name "Net-(J10-Pad3)") (class "Default")
      (node (ref "J10") (pin "3") (pinfunction "3_3") (pintype "passive"))
      (node (ref "R23") (pin "2") (pinfunction "2_2") (pintype "passive"))
      (node (ref "R25") (pin "2") (pinfunction "2_2") (pintype "passive"))
    )
    (net (code "41") (name "Net-(J11-Pad3)") (class "Default")
      (node (ref "J11") (pin "3") (pinfunction "3_3") (pintype "passive"))
      (node (ref "R24") (pin "2") (pinfunction "2_2") (pintype "passive"))
      (node (ref "R28") (pin "2") (pinfunction "2_2") (pintype "passive"))
    )
    (net (code "42") (name "Net-(J13-Pad3)") (class "Default")
      (node (ref "J13") (pin "3") (pinfunction "3_3") (pintype "passive"))
      (node (ref "R33") (pin "2") (pinfunction "2_2") (pintype "passive"))
      (node (ref "R35") (pin "2") (pinfunction "2_2") (pintype "passive"))
    )
    (net (code "43") (name "Net-(J14-Pad3)") (class "Default")
      (node (ref "J14") (pin "3") (pinfunction "3_3") (pintype "passive"))
      (node (ref "R34") (pin "2") (pinfunction "2_2") (pintype "passive"))
      (node (ref "R38") (pin "2") (pinfunction "2_2") (pintype "passive"))
    )
    (net (code "44") (name "Net-(J16-Pad3)") (class "Default")
      (node (ref "J16") (pin "3") (pinfunction "3_3") (pintype "passive"))
      (node (ref "R43") (pin "2") (pinfunction "2_2") (pintype "passive"))
      (node (ref "R45") (pin "2") (pinfunction "2_2") (pintype "passive"))
    )
    (net (code "45") (name "Net-(J17-Pad3)") (class "Default")
      (node (ref "J17") (pin "3") (pinfunction "3_3") (pintype "passive"))
      (node (ref "R44") (pin "2") (pinfunction "2_2") (pintype "passive"))
      (node (ref "R48") (pin "2") (pinfunction "2_2") (pintype "passive"))
    )
    (net (code "46") (name "Net-(Q2-D)") (class "Default")
      (node (ref "J7") (pin "4") (pinfunction "4_4") (pintype "passive"))
      (node (ref "Q2") (pin "3") (pinfunction "D_3") (pintype "bidirectional"))
    )
    (net (code "47") (name "Net-(Q2-G)") (class "Default")
      (node (ref "Q2") (pin "1") (pinfunction "G_1") (pintype "bidirectional"))
      (node (ref "R8") (pin "2") (pinfunction "2_2") (pintype "passive"))
      (node (ref "R9") (pin "2") (pinfunction "2_2") (pintype "passive"))
    )
    (net (code "48") (name "Net-(Q4-D)") (class "Default")
      (node (ref "J8") (pin "4") (pinfunction "4_4") (pintype "passive"))
      (node (ref "Q4") (pin "3") (pinfunction "D_3") (pintype "bidirectional"))
    )
    (net (code "49") (name "Net-(Q4-G)") (class "Default")
      (node (ref "Q4") (pin "1") (pinfunction "G_1") (pintype "bidirectional"))
      (node (ref "R11") (pin "2") (pinfunction "2_2") (pintype "passive"))
      (node (ref "R12") (pin "2") (pinfunction "2_2") (pintype "passive"))
    )
    (net (code "50") (name "Net-(Q5-D)") (class "Default")
      (node (ref "J10") (pin "4") (pinfunction "4_4") (pintype "passive"))
      (node (ref "Q5") (pin "3") (pinfunction "D_3") (pintype "bidirectional"))
    )
    (net (code "51") (name "Net-(Q5-G)") (class "Default")
      (node (ref "Q5") (pin "1") (pinfunction "G_1") (pintype "bidirectional"))
      (node (ref "R26") (pin "2") (pinfunction "2_2") (pintype "passive"))
      (node (ref "R27") (pin "2") (pinfunction "2_2") (pintype "passive"))
    )
    (net (code "52") (name "Net-(Q6-D)") (class "Default")
      (node (ref "J11") (pin "4") (pinfunction "4_4") (pintype "passive"))
      (node (ref "Q6") (pin "3") (pinfunction "D_3") (pintype "bidirectional"))
    )
    (net (code "53") (name "Net-(Q6-G)") (class "Default")
      (node (ref "Q6") (pin "1") (pinfunction "G_1") (pintype "bidirectional"))
      (node (ref "R29") (pin "2") (pinfunction "2_2") (pintype "passive"))
      (node (ref "R30") (pin "2") (pinfunction "2_2") (pintype "passive"))
    )
    (net (code "54") (name "Net-(Q7-D)") (class "Default")
      (node (ref "J13") (pin "4") (pinfunction "4_4") (pintype "passive"))
      (node (ref "Q7") (pin "3") (pinfunction "D_3") (pintype "bidirectional"))
    )
    (net (code "55") (name "Net-(Q7-G)") (class "Default")
      (node (ref "Q7") (pin "1") (pinfunction "G_1") (pintype "bidirectional"))
      (node (ref "R36") (pin "2") (pinfunction "2_2") (pintype "passive"))
      (node (ref "R37") (pin "2") (pinfunction "2_2") (pintype "passive"))
    )
    (net (code "56") (name "Net-(Q8-D)") (class "Default")
      (node (ref "J14") (pin "4") (pinfunction "4_4") (pintype "passive"))
      (node (ref "Q8") (pin "3") (pinfunction "D_3") (pintype "bidirectional"))
    )
    (net (code "57") (name "Net-(Q8-G)") (class "Default")
      (node (ref "Q8") (pin "1") (pinfunction "G_1") (pintype "bidirectional"))
      (node (ref "R39") (pin "2") (pinfunction "2_2") (pintype "passive"))
      (node (ref "R40") (pin "2") (pinfunction "2_2") (pintype "passive"))
    )
    (net (code "58") (name "Net-(Q9-D)") (class "Default")
      (node (ref "J16") (pin "4") (pinfunction "4_4") (pintype "passive"))
      (node (ref "Q9") (pin "3") (pinfunction "D_3") (pintype "bidirectional"))
    )
    (net (code "59") (name "Net-(Q9-G)") (class "Default")
      (node (ref "Q9") (pin "1") (pinfunction "G_1") (pintype "bidirectional"))
      (node (ref "R46") (pin "2") (pinfunction "2_2") (pintype "passive"))
      (node (ref "R47") (pin "2") (pinfunction "2_2") (pintype "passive"))
    )
    (net (code "60") (name "Net-(Q10-D)") (class "Default")
      (node (ref "J17") (pin "4") (pinfunction "4_4") (pintype "passive"))
      (node (ref "Q10") (pin "3") (pinfunction "D_3") (pintype "bidirectional"))
    )
    (net (code "61") (name "Net-(Q10-G)") (class "Default")
      (node (ref "Q10") (pin "1") (pinfunction "G_1") (pintype "bidirectional"))
      (node (ref "R49") (pin "2") (pinfunction "2_2") (pintype "passive"))
      (node (ref "R50") (pin "2") (pinfunction "2_2") (pintype "passive"))
    )
    (net (code "62") (name "Net-(U1-C1)") (class "Default")
      (node (ref "R6") (pin "1") (pinfunction "1_1") (pintype "passive"))
      (node (ref "U1") (pin "2") (pinfunction "C1_2") (pintype "bidirectional"))
    )
    (net (code "63") (name "Net-(U1-C2)") (class "Default")
      (node (ref "R5") (pin "1") (pinfunction "1_1") (pintype "passive"))
      (node (ref "U1") (pin "4") (pinfunction "C2_4") (pintype "bidirectional"))
    )
    (net (code "64") (name "Net-(U3-C1)") (class "Default")
      (node (ref "R24") (pin "1") (pinfunction "1_1") (pintype "passive"))
      (node (ref "U3") (pin "2") (pinfunction "C1_2") (pintype "bidirectional"))
    )
    (net (code "65") (name "Net-(U3-C2)") (class "Default")
      (node (ref "R23") (pin "1") (pinfunction "1_1") (pintype "passive"))
      (node (ref "U3") (pin "4") (pinfunction "C2_4") (pintype "bidirectional"))
    )
    (net (code "66") (name "Net-(U4-C1)") (class "Default")
      (node (ref "R34") (pin "1") (pinfunction "1_1") (pintype "passive"))
      (node (ref "U4") (pin "2") (pinfunction "C1_2") (pintype "bidirectional"))
    )
    (net (code "67") (name "Net-(U4-C2)") (class "Default")
      (node (ref "R33") (pin "1") (pinfunction "1_1") (pintype "passive"))
      (node (ref "U4") (pin "4") (pinfunction "C2_4") (pintype "bidirectional"))
    )
    (net (code "68") (name "Net-(U5-C1)") (class "Default")
      (node (ref "R44") (pin "1") (pinfunction "1_1") (pintype "passive"))
      (node (ref "U5") (pin "2") (pinfunction "C1_2") (pintype "bidirectional"))
    )
    (net (code "69") (name "Net-(U5-C2)") (class "Default")
      (node (ref "R43") (pin "1") (pinfunction "1_1") (pintype "passive"))
      (node (ref "U5") (pin "4") (pinfunction "C2_4") (pintype "bidirectional"))
    )
    (net (code "70") (name "unconnected-(J1-Pad1)") (class "Default")
      (node (ref "J1") (pin "1") (pinfunction "1_1") (pintype "passive"))
    )
    (net (code "71") (name "unconnected-(J1-Pad2)") (class "Default")
      (node (ref "J1") (pin "2") (pinfunction "2_2") (pintype "passive"))
    )
    (net (code "72") (name "unconnected-(J1-Pad3)") (class "Default")
      (node (ref "J1") (pin "3") (pinfunction "3_3") (pintype "passive"))
    )
    (net (code "73") (name "unconnected-(J1-Pad4)") (class "Default")
      (node (ref "J1") (pin "4") (pinfunction "4_4") (pintype "passive"))
    )
    (net (code "74") (name "unconnected-(J1-Pad5)") (class "Default")
      (node (ref "J1") (pin "5") (pinfunction "5_5") (pintype "passive"))
    )
    (net (code "75") (name "unconnected-(J1-Pad6)") (class "Default")
      (node (ref "J1") (pin "6") (pinfunction "6_6") (pintype "passive"))
    )
    (net (code "76") (name "unconnected-(J1-Pad7)") (class "Default")
      (node (ref "J1") (pin "7") (pinfunction "7_7") (pintype "passive"))
    )
    (net (code "77") (name "unconnected-(J1-Pad8)") (class "Default")
      (node (ref "J1") (pin "8") (pinfunction "8_8") (pintype "passive"))
    )
    (net (code "78") (name "unconnected-(J1-Pad9)") (class "Default")
      (node (ref "J1") (pin "9") (pinfunction "9_9") (pintype "passive"))
    )
    (net (code "79") (name "unconnected-(J1-Pad10)") (class "Default")
      (node (ref "J1") (pin "10") (pinfunction "10_10") (pintype "passive"))
    )
    (net (code "80") (name "unconnected-(J1-Pad11)") (class "Default")
      (node (ref "J1") (pin "11") (pinfunction "11_11") (pintype "passive"))
    )
    (net (code "81") (name "unconnected-(J1-Pad12)") (class "Default")
      (node (ref "J1") (pin "12") (pinfunction "12_12") (pintype "passive"))
    )
    (net (code "82") (name "unconnected-(J1-Pad13)") (class "Default")
      (node (ref "J1") (pin "13") (pinfunction "13_13") (pintype "passive"))
    )
    (net (code "83") (name "unconnected-(J1-Pad14)") (class "Default")
      (node (ref "J1") (pin "14") (pinfunction "14_14") (pintype "passive"))
    )
    (net (code "84") (name "unconnected-(J1-Pad15)") (class "Default")
      (node (ref "J1") (pin "15") (pinfunction "15_15") (pintype "passive"))
    )
    (net (code "85") (name "unconnected-(J1-Pad16)") (class "Default")
      (node (ref "J1") (pin "16") (pinfunction "16_16") (pintype "passive"))
    )
    (net (code "86") (name "unconnected-(J1-Pad17)") (class "Default")
      (node (ref "J1") (pin "17") (pinfunction "17_17") (pintype "passive"))
    )
    (net (code "87") (name "unconnected-(J1-Pad18)") (class "Default")
      (node (ref "J1") (pin "18") (pinfunction "18_18") (pintype "passive"))
    )
    (net (code "88") (name "unconnected-(J1-Pad19)") (class "Default")
      (node (ref "J1") (pin "19") (pinfunction "19_19") (pintype "passive"))
    )
    (net (code "89") (name "unconnected-(J1-Pad20)") (class "Default")
      (node (ref "J1") (pin "20") (pinfunction "20_20") (pintype "passive"))
    )
    (net (code "90") (name "unconnected-(J1-Pad21)") (class "Default")
      (node (ref "J1") (pin "21") (pinfunction "21_21") (pintype "passive"))
    )
    (net (code "91") (name "unconnected-(J1-Pad22)") (class "Default")
      (node (ref "J1") (pin "22") (pinfunction "22_22") (pintype "passive"))
    )
    (net (code "92") (name "unconnected-(J1-Pad23)") (class "Default")
      (node (ref "J1") (pin "23") (pinfunction "23_23") (pintype "passive"))
    )
    (net (code "93") (name "unconnected-(J1-Pad24)") (class "Default")
      (node (ref "J1") (pin "24") (pinfunction "24_24") (pintype "passive"))
    )
    (net (code "94") (name "unconnected-(J2-Pad1)") (class "Default")
      (node (ref "J2") (pin "1") (pinfunction "1_1") (pintype "passive"))
    )
    (net (code "95") (name "unconnected-(J2-Pad2)") (class "Default")
      (node (ref "J2") (pin "2") (pinfunction "2_2") (pintype "passive"))
    )
    (net (code "96") (name "unconnected-(J2-Pad3)") (class "Default")
      (node (ref "J2") (pin "3") (pinfunction "3_3") (pintype "passive"))
    )
    (net (code "97") (name "unconnected-(J2-Pad4)") (class "Default")
      (node (ref "J2") (pin "4") (pinfunction "4_4") (pintype "passive"))
    )
    (net (code "98") (name "unconnected-(J2-Pad5)") (class "Default")
      (node (ref "J2") (pin "5") (pinfunction "5_5") (pintype "passive"))
    )
    (net (code "99") (name "unconnected-(J2-Pad6)") (class "Default")
      (node (ref "J2") (pin "6") (pinfunction "6_6") (pintype "passive"))
    )
    (net (code "100") (name "unconnected-(J2-Pad7)") (class "Default")
      (node (ref "J2") (pin "7") (pinfunction "7_7") (pintype "passive"))
    )
    (net (code "101") (name "unconnected-(J2-Pad8)") (class "Default")
      (node (ref "J2") (pin "8") (pinfunction "8_8") (pintype "passive"))
    )
    (net (code "102") (name "unconnected-(J2-Pad9)") (class "Default")
      (node (ref "J2") (pin "9") (pinfunction "9_9") (pintype "passive"))
    )
    (net (code "103") (name "unconnected-(J2-Pad10)") (class "Default")
      (node (ref "J2") (pin "10") (pinfunction "10_10") (pintype "passive"))
    )
    (net (code "104") (name "unconnected-(J2-Pad11)") (class "Default")
      (node (ref "J2") (pin "11") (pinfunction "11_11") (pintype "passive"))
    )
    (net (code "105") (name "unconnected-(J2-Pad12)") (class "Default")
      (node (ref "J2") (pin "12") (pinfunction "12_12") (pintype "passive"))
    )
    (net (code "106") (name "unconnected-(J2-Pad13)") (class "Default")
      (node (ref "J2") (pin "13") (pinfunction "13_13") (pintype "passive"))
    )
    (net (code "107") (name "unconnected-(J2-Pad14)") (class "Default")
      (node (ref "J2") (pin "14") (pinfunction "14_14") (pintype "passive"))
    )
    (net (code "108") (name "unconnected-(J2-Pad15)") (class "Default")
      (node (ref "J2") (pin "15") (pinfunction "15_15") (pintype "passive"))
    )
    (net (code "109") (name "unconnected-(J2-Pad16)") (class "Default")
      (node (ref "J2") (pin "16") (pinfunction "16_16") (pintype "passive"))
    )
    (net (code "110") (name "unconnected-(J2-Pad17)") (class "Default")
      (node (ref "J2") (pin "17") (pinfunction "17_17") (pintype "passive"))
    )
    (net (code "111") (name "unconnected-(J2-Pad18)") (class "Default")
      (node (ref "J2") (pin "18") (pinfunction "18_18") (pintype "passive"))
    )
    (net (code "112") (name "unconnected-(J2-Pad19)") (class "Default")
      (node (ref "J2") (pin "19") (pinfunction "19_19") (pintype "passive"))
    )
    (net (code "113") (name "unconnected-(J2-Pad20)") (class "Default")
      (node (ref "J2") (pin "20") (pinfunction "20_20") (pintype "passive"))
    )
    (net (code "114") (name "unconnected-(J2-Pad21)") (class "Default")
      (node (ref "J2") (pin "21") (pinfunction "21_21") (pintype "passive"))
    )
    (net (code "115") (name "unconnected-(J2-Pad22)") (class "Default")
      (node (ref "J2") (pin "22") (pinfunction "22_22") (pintype "passive"))
    )
    (net (code "116") (name "unconnected-(J2-Pad23)") (class "Default")
      (node (ref "J2") (pin "23") (pinfunction "23_23") (pintype "passive"))
    )
    (net (code "117") (name "unconnected-(J2-Pad24)") (class "Default")
      (node (ref "J2") (pin "24") (pinfunction "24_24") (pintype "passive"))
    )
    (net (code "118") (name "unconnected-(U$1-25-A11{slash}RX6{slash}SDA2-Pad25-A11{slash}SDA2)") (class "Default")
      (node (ref "U$1") (pin "25-A11/SDA2") (pinfunction "25-A11/RX6/SDA2_25-A11/SDA2") (pintype "bidirectional"))
    )
    (net (code "119") (name "unconnected-(U$1-32-OUT1B-Pad32-OUTB1)") (class "Default")
      (node (ref "U$1") (pin "32-OUTB1") (pinfunction "32-OUT1B_32-OUTB1") (pintype "bidirectional"))
    )
    (net (code "120") (name "unconnected-(U$1-Pad3V3-2)") (class "Default")
      (node (ref "U$1") (pin "3V3-2") (pinfunction "3V3-2_3V3-2") (pintype "bidirectional"))
    )
    (net (code "121") (name "unconnected-(U$1-Pad13-SCK{slash}CRX1{slash}LED)") (class "Default")
      (node (ref "U$1") (pin "13-SCK/CRX1/LED") (pinfunction "13-SCK/CRX1/LED_13-SCK/CRX1/LED") (pintype "bidirectional"))
    )
    (net (code "122") (name "unconnected-(U$1-Pad24-A10{slash}TX6{slash}SCL2)") (class "Default")
      (node (ref "U$1") (pin "24-A10/TX6/SCL2") (pinfunction "24-A10/TX6/SCL2_24-A10/TX6/SCL2") (pintype "bidirectional"))
    )
    (net (code "123") (name "unconnected-(U$1-Pad26-A12{slash}MOSI1)") (class "Default")
      (node (ref "U$1") (pin "26-A12/MOSI1") (pinfunction "26-A12/MOSI1_26-A12/MOSI1") (pintype "bidirectional"))
    )
    (net (code "124") (name "unconnected-(U$1-Pad27-A13{slash}SCK1)") (class "Default")
      (node (ref "U$1") (pin "27-A13/SCK1") (pinfunction "27-A13/SCK1_27-A13/SCK1") (pintype "bidirectional"))
    )
    (net (code "125") (name "unconnected-(U$1-Pad28-RX7)") (class "Default")
      (node (ref "U$1") (pin "28-RX7") (pinfunction "28-RX7_28-RX7") (pintype "bidirectional"))
    )
    (net (code "126") (name "unconnected-(U$1-Pad29-TX7)") (class "Default")
      (node (ref "U$1") (pin "29-TX7") (pinfunction "29-TX7_29-TX7") (pintype "bidirectional"))
    )
    (net (code "127") (name "unconnected-(U$1-Pad30-CRX3)") (class "Default")
      (node (ref "U$1") (pin "30-CRX3") (pinfunction "30-CRX3_30-CRX3") (pintype "bidirectional"))
    )
    (net (code "128") (name "unconnected-(U$1-Pad31-CTX3)") (class "Default")
      (node (ref "U$1") (pin "31-CTX3") (pinfunction "31-CTX3_31-CTX3") (pintype "bidirectional"))
    )
    (net (code "129") (name "unconnected-(U$1-Pad33-MCLK2)") (class "Default")
      (node (ref "U$1") (pin "33-MCLK2") (pinfunction "33-MCLK2_33-MCLK2") (pintype "bidirectional"))
    )
    (net (code "130") (name "unconnected-(U$1-PadD+)") (class "Default")
      (node (ref "U$1") (pin "D+") (pinfunction "D+_D+") (pintype "bidirectional"))
    )
    (net (code "131") (name "unconnected-(U$1-PadD-)") (class "Default")
      (node (ref "U$1") (pin "D-") (pinfunction "D-_D-") (pintype "bidirectional"))
    )
    (net (code "132") (name "unconnected-(U$1-PadGND2)") (class "Default")
      (node (ref "U$1") (pin "GND2") (pinfunction "GND2_GND2") (pintype "bidirectional"))
    )
    (net (code "133") (name "unconnected-(U$1-PadGND3)") (class "Default")
      (node (ref "U$1") (pin "GND3") (pinfunction "GND3_GND3") (pintype "bidirectional"))
    )
    (net (code "134") (name "unconnected-(U$1-PadON{slash}OFF)") (class "Default")
      (node (ref "U$1") (pin "ON/OFF") (pinfunction "ON/OFF_ON/OFF") (pintype "bidirectional"))
    )
    (net (code "135") (name "unconnected-(U$1-PadPROGRAM)") (class "Default")
      (node (ref "U$1") (pin "PROGRAM") (pinfunction "PROGRAM_PROGRAM") (pintype "bidirectional"))
    )
    (net (code "136") (name "unconnected-(U$1-PadVBAT)") (class "Default")
      (node (ref "U$1") (pin "VBAT") (pinfunction "VBAT_VBAT") (pintype "bidirectional"))
    )
    (net (code "137") (name "unconnected-(U$1-PadVUSB)") (class "Default")
      (node (ref "U$1") (pin "VUSB") (pinfunction "VUSB_VUSB") (pintype "bidirectional"))
    )
  )
)
